# main.net
KiCad netlist of a schematic drawn in EAGLE
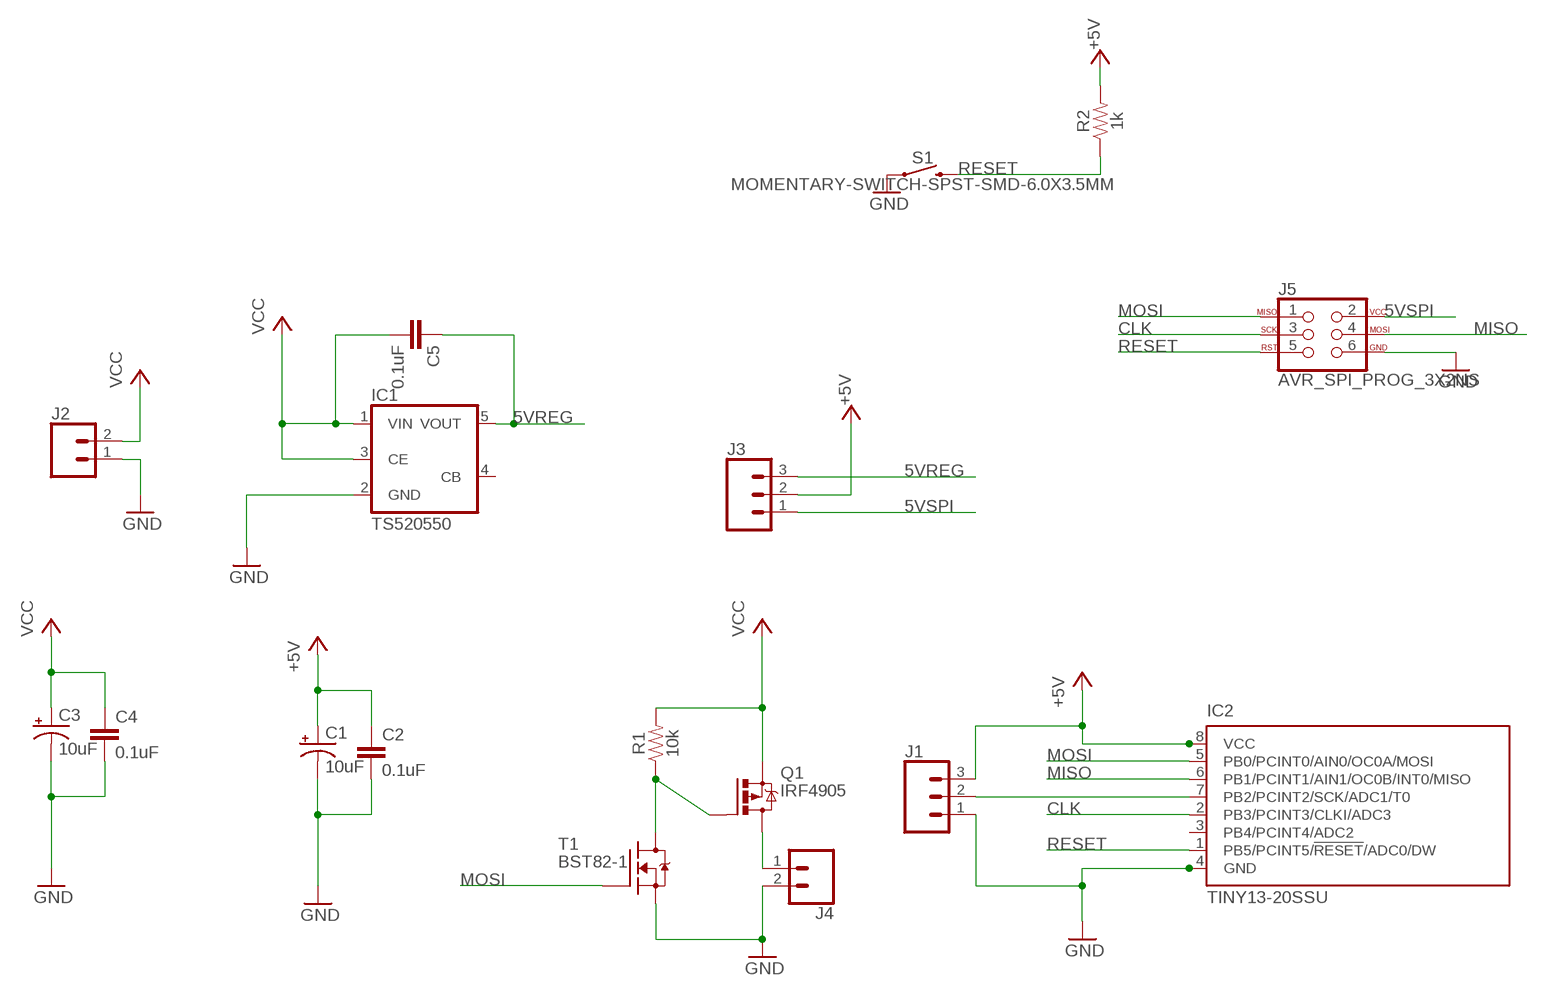
[diagram p0: schematic, sheet 1]

(export (version "E")
  (design (tool "Eeschema 10.0.6"))
  (components
    (comp (ref "C1")
      (value "10uF")
      (footprint "eagle-import:CPOL-RADIAL-2.5MM-5MM")
      (libsource (lib "eagle-import") (part "10UF-POLAR-RADIAL-2.5MM-25V-20%"))
    )
    (comp (ref "C2")
      (value "0.1uF")
      (footprint "eagle-import:0603")
      (libsource (lib "eagle-import") (part "0.1UF-0603-25V-5%"))
    )
    (comp (ref "C3")
      (value "10uF")
      (footprint "eagle-import:CPOL-RADIAL-2.5MM-5MM")
      (libsource (lib "eagle-import") (part "10UF-POLAR-RADIAL-2.5MM-25V-20%"))
    )
    (comp (ref "C4")
      (value "0.1uF")
      (footprint "eagle-import:0603")
      (libsource (lib "eagle-import") (part "0.1UF-0603-25V-5%"))
    )
    (comp (ref "C5")
      (value "0.1uF")
      (footprint "eagle-import:0603")
      (libsource (lib "eagle-import") (part "0.1UF-0603-25V-5%"))
    )
    (comp (ref "IC1")
      (value "TS520550")
      (footprint "eagle-import:SOT25")
      (libsource (lib "eagle-import") (part "TS520550"))
    )
    (comp (ref "IC2")
      (value "TINY13-20SSU")
      (footprint "eagle-import:8S1")
      (fields (field (name "MPN") "ATTINY13-20SSU"))
      (libsource (lib "eagle-import") (part "TINY13SSU-20"))
    )
    (comp (ref "J1")
      (value "CONN_03")
      (footprint "eagle-import:1X03")
      (libsource (lib "eagle-import") (part "CONN_03"))
    )
    (comp (ref "J2")
      (value "CONN_023.5MM_LOCK")
      (footprint "eagle-import:SCREWTERMINAL-3.5MM-2_LOCK")
      (libsource (lib "eagle-import") (part "CONN_023.5MM_LOCK"))
    )
    (comp (ref "J3")
      (value "CONN_03")
      (footprint "eagle-import:1X03")
      (libsource (lib "eagle-import") (part "CONN_03"))
    )
    (comp (ref "J4")
      (value "CONN_023.5MM")
      (footprint "eagle-import:SCREWTERMINAL-3.5MM-2")
      (libsource (lib "eagle-import") (part "CONN_023.5MM"))
    )
    (comp (ref "J5")
      (value "AVR_SPI_PROG_3X2NS")
      (footprint "eagle-import:2X3-NS")
      (libsource (lib "eagle-import") (part "AVR_SPI_PROG_3X2NS"))
    )
    (comp (ref "Q1")
      (value "IRF4905")
      (footprint "eagle-import:TO220BH")
      (libsource (lib "eagle-import") (part "IRF4905"))
    )
    (comp (ref "R1")
      (value "10k")
      (footprint "eagle-import:0603")
      (libsource (lib "eagle-import") (part "10KOHM-0603-1/10W-1%"))
    )
    (comp (ref "R2")
      (value "1k")
      (footprint "eagle-import:0603")
      (libsource (lib "eagle-import") (part "1KOHM-0603-1/10W-1%"))
    )
    (comp (ref "S1")
      (value "MOMENTARY-SWITCH-SPST-SMD-6.0X3.5MM")
      (footprint "eagle-import:TACTILE_SWITCH_SMD_6.0X3.5MM")
      (libsource (lib "eagle-import") (part "MOMENTARY-SWITCH-SPST-SMD-6.0X3.5MM"))
    )
    (comp (ref "T1")
      (value "BST82-1")
      (footprint "eagle-import:SOT23")
      (libsource (lib "eagle-import") (part "BST82-1"))
    )
  )
  (nets
    (net (code "1") (name "+5V") (class "Default")
      (node (ref "C1") (pin "1") (pinfunction "+_1") (pintype "passive"))
      (node (ref "C2") (pin "1") (pinfunction "1_1") (pintype "passive"))
      (node (ref "IC2") (pin "8") (pinfunction "VCC_8") (pintype "power_in"))
      (node (ref "J1") (pin "3") (pinfunction "3_3") (pintype "passive"))
      (node (ref "J3") (pin "2") (pinfunction "2_2") (pintype "passive"))
      (node (ref "R2") (pin "2") (pinfunction "2_2") (pintype "passive"))
    )
    (net (code "2") (name "/5VREG") (class "Default")
      (node (ref "C5") (pin "1") (pinfunction "1_1") (pintype "passive"))
      (node (ref "IC1") (pin "5") (pinfunction "VOUT_5") (pintype "passive"))
      (node (ref "J3") (pin "3") (pinfunction "3_3") (pintype "passive"))
    )
    (net (code "3") (name "/5VSPI") (class "Default")
      (node (ref "J3") (pin "1") (pinfunction "1_1") (pintype "passive"))
      (node (ref "J5") (pin "2") (pinfunction "2_2") (pintype "passive"))
    )
    (net (code "4") (name "/CLK") (class "Default")
      (node (ref "IC2") (pin "2") (pinfunction "PB3/PCINT3/CLKI/ADC3_2") (pintype "bidirectional"))
      (node (ref "J5") (pin "3") (pinfunction "3_3") (pintype "passive"))
    )
    (net (code "5") (name "/MISO") (class "Default")
      (node (ref "IC2") (pin "6") (pinfunction "PB1/PCINT1/AIN1/OC0B/INT0/MISO_6") (pintype "bidirectional"))
      (node (ref "J5") (pin "4") (pinfunction "4_4") (pintype "passive"))
    )
    (net (code "6") (name "/MOSI") (class "Default")
      (node (ref "IC2") (pin "5") (pinfunction "PB0/PCINT0/AIN0/OC0A/MOSI_5") (pintype "bidirectional"))
      (node (ref "J5") (pin "1") (pinfunction "1_1") (pintype "passive"))
      (node (ref "T1") (pin "1") (pinfunction "G_1") (pintype "passive"))
    )
    (net (code "7") (name "/RESET") (class "Default")
      (node (ref "IC2") (pin "1") (pinfunction "PB5/PCINT5/~{RESET}/ADC0/DW_1") (pintype "bidirectional"))
      (node (ref "J5") (pin "5") (pinfunction "5_5") (pintype "passive"))
      (node (ref "R2") (pin "1") (pinfunction "1_1") (pintype "passive"))
      (node (ref "S1") (pin "2") (pinfunction "2_2") (pintype "passive"))
    )
    (net (code "8") (name "GND") (class "Default")
      (node (ref "C1") (pin "2") (pinfunction "-_2") (pintype "passive"))
      (node (ref "C2") (pin "2") (pinfunction "2_2") (pintype "passive"))
      (node (ref "C3") (pin "2") (pinfunction "-_2") (pintype "passive"))
      (node (ref "C4") (pin "2") (pinfunction "2_2") (pintype "passive"))
      (node (ref "IC1") (pin "2") (pinfunction "GND_2") (pintype "passive"))
      (node (ref "IC2") (pin "4") (pinfunction "GND_4") (pintype "power_in"))
      (node (ref "J1") (pin "1") (pinfunction "1_1") (pintype "passive"))
      (node (ref "J2") (pin "1") (pinfunction "1_1") (pintype "passive"))
      (node (ref "J4") (pin "2") (pinfunction "2_2") (pintype "passive"))
      (node (ref "J5") (pin "6") (pinfunction "6_6") (pintype "passive"))
      (node (ref "S1") (pin "1") (pinfunction "1_1") (pintype "passive"))
      (node (ref "T1") (pin "2") (pinfunction "S_2") (pintype "passive"))
    )
    (net (code "9") (name "Net-(IC2-PB2{slash}PCINT2{slash}SCK{slash}ADC1{slash}T0)") (class "Default")
      (node (ref "IC2") (pin "7") (pinfunction "PB2/PCINT2/SCK/ADC1/T0_7") (pintype "bidirectional"))
      (node (ref "J1") (pin "2") (pinfunction "2_2") (pintype "passive"))
    )
    (net (code "10") (name "Net-(J4-Pad1)") (class "Default")
      (node (ref "J4") (pin "1") (pinfunction "1_1") (pintype "passive"))
      (node (ref "Q1") (pin "D") (pinfunction "D_D") (pintype "passive"))
    )
    (net (code "11") (name "Net-(T1-D)") (class "Default")
      (node (ref "Q1") (pin "G") (pinfunction "G_G") (pintype "passive"))
      (node (ref "R1") (pin "1") (pinfunction "1_1") (pintype "passive"))
      (node (ref "T1") (pin "3") (pinfunction "D_3") (pintype "passive"))
    )
    (net (code "12") (name "VCC") (class "Default")
      (node (ref "C3") (pin "1") (pinfunction "+_1") (pintype "passive"))
      (node (ref "C4") (pin "1") (pinfunction "1_1") (pintype "passive"))
      (node (ref "C5") (pin "2") (pinfunction "2_2") (pintype "passive"))
      (node (ref "IC1") (pin "1") (pinfunction "VIN_1") (pintype "input"))
      (node (ref "IC1") (pin "3") (pinfunction "CE_3") (pintype "input"))
      (node (ref "J2") (pin "2") (pinfunction "2_2") (pintype "passive"))
      (node (ref "Q1") (pin "S") (pinfunction "S_S") (pintype "passive"))
      (node (ref "R1") (pin "2") (pinfunction "2_2") (pintype "passive"))
    )
    (net (code "13") (name "unconnected-(IC1-CB-Pad4)") (class "Default")
      (node (ref "IC1") (pin "4") (pinfunction "CB_4") (pintype "input"))
    )
    (net (code "14") (name "unconnected-(IC2-PB4{slash}PCINT4{slash}ADC2-Pad3)") (class "Default")
      (node (ref "IC2") (pin "3") (pinfunction "PB4/PCINT4/ADC2_3") (pintype "bidirectional"))
    )
  )
)
